# 5V_Buck_Schematic.net
KiCad netlist of a schematic drawn in Altium Designer
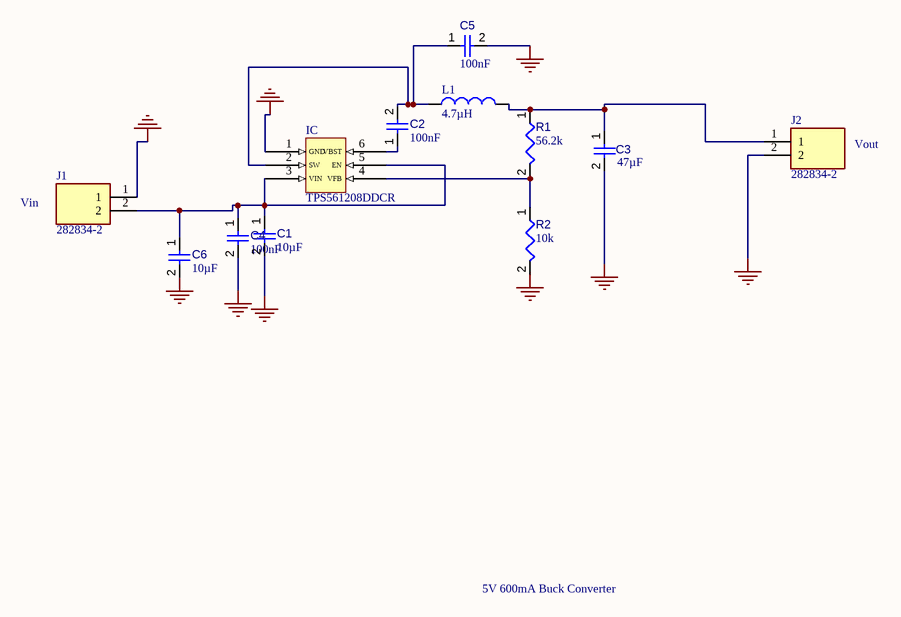
[diagram p0: 5V_Buck_Schematic.SchDoc]

(export (version "E")
  (design (tool "Eeschema 10.0.6"))
  (components
    (comp (ref "C1")
      (value "10µF")
      (footprint "CAPC2012X14N")
      (fields (field (name "Comment") "MSAST21GBB5106MTNA01"))
      (libsource (lib "Joshua Teele") (part "CAP-NP-2"))
    )
    (comp (ref "C2")
      (value "100nF")
      (footprint "CAPC2012X06N")
      (description "0805 100 nF 25V ±10 % Tolerance X7R Surface Mount Multilayer Ceramic Capacitor")
      (fields (field (name "TOLERANCE") "10%") (field (name "Comment") "08053C104KAT2A"))
      (libsource (lib "Joshua Teele") (part "CAP-NP-2"))
    )
    (comp (ref "C3")
      (value "47µF")
      (footprint "CAPC3225X27N")
      (description "Capacitor: ceramic; MLCC; 47uF; 16V; X5R; ±10%; SMD; 1210; Series: GRM")
      (fields (field (name "VOLTAGE") "16V") (field (name "TOLERANCE") "10%"))
      (libsource (lib "Joshua Teele") (part "CAP-NP-2"))
    )
    (comp (ref "C4")
      (value "100nF")
      (footprint "CAPC1005X56X25LL10T15")
      (description "Chip Capacitor, 0.1 uF, +/- 5%, 16 V, 0402 (1005 Metric)")
      (fields (field (name "TOLERANCE") "5%") (field (name "Comment") "Capacitor 0.1 uF +/- 5% 16 V 0402"))
      (libsource (lib "Joshua Teele") (part "CAP-NP-2"))
    )
    (comp (ref "C5")
      (value "100nF")
      (footprint "CAPC1005X56X25LL10T15")
      (description "Chip Capacitor, 0.1 uF, +/- 5%, 16 V, 0402 (1005 Metric)")
      (fields (field (name "TOLERANCE") "5%") (field (name "Comment") "Capacitor 0.1 uF +/- 5% 16 V 0402"))
      (libsource (lib "Joshua Teele") (part "CAP-NP-2"))
    )
    (comp (ref "C6")
      (value "10µF")
      (footprint "CAPC2012X14N")
      (fields (field (name "Comment") "MSAST21GBB5106MTNA01"))
      (libsource (lib "Joshua Teele") (part "CAP-NP-2"))
    )
    (comp (ref "IC")
      (value "TPS561208DDCR")
      (footprint "SOT95P245X110-6N")
      (description "4.5V to 17V Input, 1A Output, Synchronous Step-Down Converter 6-SOT-23-THIN -40 to 125")
      (libsource (lib "Joshua Teele") (part "TPS561208DDCR-Symbol-1"))
    )
    (comp (ref "J1")
      (value "282834-2")
      (footprint "TE_282834-2")
      (description "Terminal Block Connector PCB 2.54 mm 30-16 AWG Green 10 A 150 V M1.6")
      (fields (field (name "MF") "TE Connectivity"))
      (libsource (lib "Joshua Teele") (part "282834-2"))
    )
    (comp (ref "J2")
      (value "282834-2")
      (footprint "TE_282834-2")
      (description "Terminal Block Connector PCB 2.54 mm 30-16 AWG Green 10 A 150 V M1.6")
      (fields (field (name "MF") "TE Connectivity"))
      (libsource (lib "") (part "282834-2_1"))
    )
    (comp (ref "L1")
      (value "4.7µH")
      (footprint "INDP3030X15N")
      (description "Inductor Power Shielded Wirewound 4.7uH 20% 1MHz Ferrite 1.35A 136mOhm DCR 1212 Blister T/R")
      (fields (field (name "TOLERANCE") "20%") (field (name "Comment") "VLS3015ET-4R7M"))
      (libsource (lib "Joshua Teele") (part "IND-2"))
    )
    (comp (ref "R1")
      (value "56.2k")
      (footprint "RESC2012X07N")
      (description "Res Thick Film 0805 56.2K Ohm 1% 0.125W(1/8W) ±100ppm/°C Molded SMD Punched Carrier T/R")
      (fields (field (name "TOLERANCE") "1%") (field (name "Comment") "ERJ-6ENF5622V"))
      (libsource (lib "Joshua Teele") (part "RES-2"))
    )
    (comp (ref "R2")
      (value "10k")
      (footprint "RESC3216X60X45ML15T20")
      (description "Chip Resistor, 10 KOhm, +/- 1%, 0.25 W, -55 to 155 degC, 1206 (3216 Metric)")
      (fields (field (name "TOLERANCE") "1%") (field (name "POWER") "250mW"))
      (libsource (lib "Joshua Teele") (part "RES-2"))
    )
  )
  (nets
    (net (code "1") (name "GND") (class "Default")
      (node (ref "C1") (pin "2") (pinfunction "2_2") (pintype "passive"))
      (node (ref "C3") (pin "2") (pinfunction "2_2") (pintype "passive"))
      (node (ref "C4") (pin "2") (pinfunction "2_2") (pintype "passive"))
      (node (ref "C5") (pin "2") (pinfunction "2_2") (pintype "passive"))
      (node (ref "C6") (pin "2") (pinfunction "2_2") (pintype "passive"))
      (node (ref "IC") (pin "1") (pinfunction "GND_1") (pintype "input"))
      (node (ref "J1") (pin "1") (pinfunction "1_1") (pintype "passive"))
      (node (ref "J2") (pin "2") (pinfunction "2_2") (pintype "passive"))
      (node (ref "R2") (pin "2") (pinfunction "2_2") (pintype "passive"))
    )
    (net (code "2") (name "Net-(C3-Pad1)") (class "Default")
      (node (ref "C3") (pin "1") (pinfunction "1_1") (pintype "passive"))
      (node (ref "J2") (pin "1") (pinfunction "1_1") (pintype "passive"))
      (node (ref "L1") (pin "2") (pinfunction "2_2") (pintype "passive"))
      (node (ref "R1") (pin "1") (pinfunction "1_1") (pintype "passive"))
    )
    (net (code "3") (name "Net-(IC-EN)") (class "Default")
      (node (ref "C1") (pin "1") (pinfunction "1_1") (pintype "passive"))
      (node (ref "C4") (pin "1") (pinfunction "1_1") (pintype "passive"))
      (node (ref "C6") (pin "1") (pinfunction "1_1") (pintype "passive"))
      (node (ref "IC") (pin "3") (pinfunction "VIN_3") (pintype "input"))
      (node (ref "IC") (pin "5") (pinfunction "EN_5") (pintype "input"))
      (node (ref "J1") (pin "2") (pinfunction "2_2") (pintype "passive"))
    )
    (net (code "4") (name "Net-(IC-SW)") (class "Default")
      (node (ref "C2") (pin "2") (pinfunction "2_2") (pintype "passive"))
      (node (ref "C5") (pin "1") (pinfunction "1_1") (pintype "passive"))
      (node (ref "IC") (pin "2") (pinfunction "SW_2") (pintype "input"))
      (node (ref "L1") (pin "1") (pinfunction "1_1") (pintype "passive"))
    )
    (net (code "5") (name "Net-(IC-VBST)") (class "Default")
      (node (ref "C2") (pin "1") (pinfunction "1_1") (pintype "passive"))
      (node (ref "IC") (pin "6") (pinfunction "VBST_6") (pintype "input"))
    )
    (net (code "6") (name "Net-(IC-VFB)") (class "Default")
      (node (ref "IC") (pin "4") (pinfunction "VFB_4") (pintype "input"))
      (node (ref "R1") (pin "2") (pinfunction "2_2") (pintype "passive"))
      (node (ref "R2") (pin "1") (pinfunction "1_1") (pintype "passive"))
    )
  )
)
